# Fidgetspinner.net
KiCad netlist of a schematic drawn in EAGLE
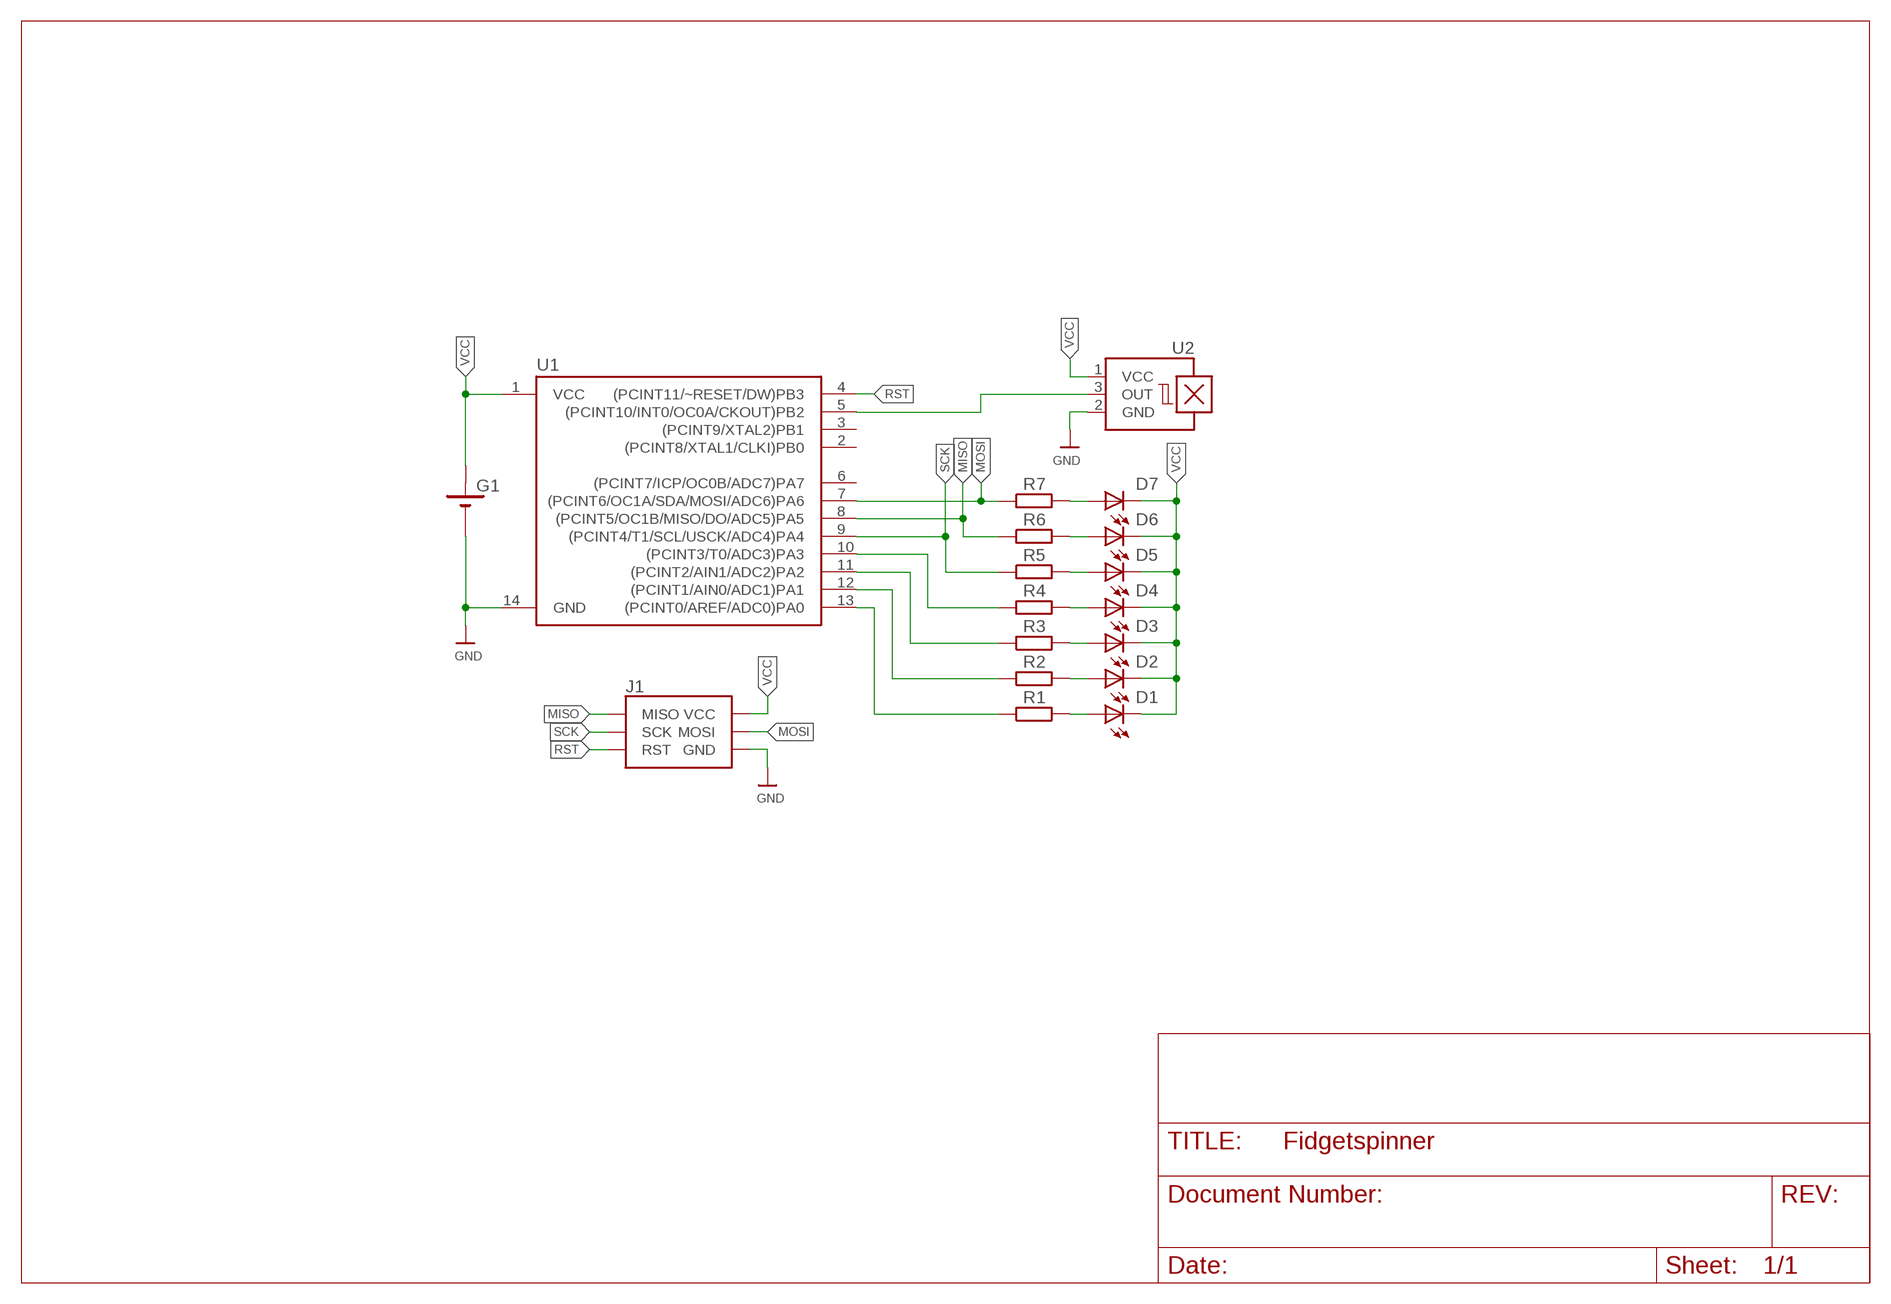
[diagram p0: schematic, sheet 1]

(export (version "E")
  (design (tool "Eeschema 10.0.6"))
  (components
    (comp (ref "D1")
      (value "LEDCHIPLED_0805")
      (footprint "eagle-import:CHIPLED_0805")
      (libsource (lib "eagle-import") (part "LEDCHIPLED_0805"))
    )
    (comp (ref "D2")
      (value "LEDCHIPLED_0805")
      (footprint "eagle-import:CHIPLED_0805")
      (libsource (lib "eagle-import") (part "LEDCHIPLED_0805"))
    )
    (comp (ref "D3")
      (value "LEDCHIPLED_0805")
      (footprint "eagle-import:CHIPLED_0805")
      (libsource (lib "eagle-import") (part "LEDCHIPLED_0805"))
    )
    (comp (ref "D4")
      (value "LEDCHIPLED_0805")
      (footprint "eagle-import:CHIPLED_0805")
      (libsource (lib "eagle-import") (part "LEDCHIPLED_0805"))
    )
    (comp (ref "D5")
      (value "LEDCHIPLED_0805")
      (footprint "eagle-import:CHIPLED_0805")
      (libsource (lib "eagle-import") (part "LEDCHIPLED_0805"))
    )
    (comp (ref "D6")
      (value "LEDCHIPLED_0805")
      (footprint "eagle-import:CHIPLED_0805")
      (libsource (lib "eagle-import") (part "LEDCHIPLED_0805"))
    )
    (comp (ref "D7")
      (value "LEDCHIPLED_0805")
      (footprint "eagle-import:CHIPLED_0805")
      (libsource (lib "eagle-import") (part "LEDCHIPLED_0805"))
    )
    (comp (ref "G1")
      (value "BATTERY")
      (footprint "eagle-import:10MM_SM_COIN_CELL_CLIP")
      (libsource (lib "eagle-import") (part "BATTERY"))
    )
    (comp (ref "J1")
      (value "SPI-HEADER2X3_LOCK")
      (footprint "eagle-import:2X3_LOCK")
      (libsource (lib "eagle-import") (part "SPI-HEADER2X3_LOCK"))
    )
    (comp (ref "R1")
      (value "RESISTOR0805")
      (footprint "eagle-import:0805")
      (libsource (lib "eagle-import") (part "RESISTOR0805"))
    )
    (comp (ref "R2")
      (value "RESISTOR0805")
      (footprint "eagle-import:0805")
      (libsource (lib "eagle-import") (part "RESISTOR0805"))
    )
    (comp (ref "R3")
      (value "RESISTOR0805")
      (footprint "eagle-import:0805")
      (libsource (lib "eagle-import") (part "RESISTOR0805"))
    )
    (comp (ref "R4")
      (value "RESISTOR0805")
      (footprint "eagle-import:0805")
      (libsource (lib "eagle-import") (part "RESISTOR0805"))
    )
    (comp (ref "R5")
      (value "RESISTOR0805")
      (footprint "eagle-import:0805")
      (libsource (lib "eagle-import") (part "RESISTOR0805"))
    )
    (comp (ref "R6")
      (value "RESISTOR0805")
      (footprint "eagle-import:0805")
      (libsource (lib "eagle-import") (part "RESISTOR0805"))
    )
    (comp (ref "R7")
      (value "RESISTOR0805")
      (footprint "eagle-import:0805")
      (libsource (lib "eagle-import") (part "RESISTOR0805"))
    )
    (comp (ref "U1")
      (value "ATTINY84ATTINY84-20PU")
      (footprint "eagle-import:DIP14")
      (libsource (lib "eagle-import") (part "ATTINY84ATTINY84-20PU"))
    )
    (comp (ref "U2")
      (value "HALL-SWITCH02UA")
      (footprint "eagle-import:SIP3-UA")
      (libsource (lib "eagle-import") (part "HALL-SWITCHUA02"))
    )
  )
  (nets
    (net (code "1") (name "GND") (class "Default")
      (node (ref "G1") (pin "-") (pinfunction "-_-") (pintype "passive"))
      (node (ref "J1") (pin "6") (pinfunction "GND_6") (pintype "passive"))
      (node (ref "U1") (pin "14") (pinfunction "GND_14") (pintype "bidirectional"))
      (node (ref "U2") (pin "2") (pinfunction "GND_2") (pintype "power_in"))
    )
    (net (code "2") (name "MISO") (class "Default")
      (node (ref "J1") (pin "1") (pinfunction "MISO_1") (pintype "passive"))
      (node (ref "R6") (pin "1") (pinfunction "1_1") (pintype "passive"))
      (node (ref "U1") (pin "8") (pinfunction "(PCINT5/OC1B/MISO/DO/ADC5)PA5_8") (pintype "bidirectional"))
    )
    (net (code "3") (name "MOSI") (class "Default")
      (node (ref "J1") (pin "4") (pinfunction "MOSI_4") (pintype "passive"))
      (node (ref "R7") (pin "1") (pinfunction "1_1") (pintype "passive"))
      (node (ref "U1") (pin "7") (pinfunction "(PCINT6/OC1A/SDA/MOSI/ADC6)PA6_7") (pintype "bidirectional"))
    )
    (net (code "4") (name "Net-(D1-PadA)") (class "Default")
      (node (ref "D1") (pin "A") (pinfunction "A_A") (pintype "passive"))
      (node (ref "R1") (pin "2") (pinfunction "2_2") (pintype "passive"))
    )
    (net (code "5") (name "Net-(D2-PadA)") (class "Default")
      (node (ref "D2") (pin "A") (pinfunction "A_A") (pintype "passive"))
      (node (ref "R2") (pin "2") (pinfunction "2_2") (pintype "passive"))
    )
    (net (code "6") (name "Net-(D3-PadA)") (class "Default")
      (node (ref "D3") (pin "A") (pinfunction "A_A") (pintype "passive"))
      (node (ref "R3") (pin "2") (pinfunction "2_2") (pintype "passive"))
    )
    (net (code "7") (name "Net-(D4-PadA)") (class "Default")
      (node (ref "D4") (pin "A") (pinfunction "A_A") (pintype "passive"))
      (node (ref "R4") (pin "2") (pinfunction "2_2") (pintype "passive"))
    )
    (net (code "8") (name "Net-(D5-PadA)") (class "Default")
      (node (ref "D5") (pin "A") (pinfunction "A_A") (pintype "passive"))
      (node (ref "R5") (pin "2") (pinfunction "2_2") (pintype "passive"))
    )
    (net (code "9") (name "Net-(D6-PadA)") (class "Default")
      (node (ref "D6") (pin "A") (pinfunction "A_A") (pintype "passive"))
      (node (ref "R6") (pin "2") (pinfunction "2_2") (pintype "passive"))
    )
    (net (code "10") (name "Net-(D7-PadA)") (class "Default")
      (node (ref "D7") (pin "A") (pinfunction "A_A") (pintype "passive"))
      (node (ref "R7") (pin "2") (pinfunction "2_2") (pintype "passive"))
    )
    (net (code "11") (name "Net-(U1-(PCINT0{slash}AREF{slash}ADC0)PA0)") (class "Default")
      (node (ref "R1") (pin "1") (pinfunction "1_1") (pintype "passive"))
      (node (ref "U1") (pin "13") (pinfunction "(PCINT0/AREF/ADC0)PA0_13") (pintype "bidirectional"))
    )
    (net (code "12") (name "Net-(U1-(PCINT1{slash}AIN0{slash}ADC1)PA1)") (class "Default")
      (node (ref "R2") (pin "1") (pinfunction "1_1") (pintype "passive"))
      (node (ref "U1") (pin "12") (pinfunction "(PCINT1/AIN0/ADC1)PA1_12") (pintype "bidirectional"))
    )
    (net (code "13") (name "Net-(U1-(PCINT2{slash}AIN1{slash}ADC2)PA2)") (class "Default")
      (node (ref "R3") (pin "1") (pinfunction "1_1") (pintype "passive"))
      (node (ref "U1") (pin "11") (pinfunction "(PCINT2/AIN1/ADC2)PA2_11") (pintype "bidirectional"))
    )
    (net (code "14") (name "Net-(U1-(PCINT3{slash}T0{slash}ADC3)PA3)") (class "Default")
      (node (ref "R4") (pin "1") (pinfunction "1_1") (pintype "passive"))
      (node (ref "U1") (pin "10") (pinfunction "(PCINT3/T0/ADC3)PA3_10") (pintype "bidirectional"))
    )
    (net (code "15") (name "Net-(U1-(PCINT10{slash}INT0{slash}OC0A{slash}CKOUT)PB2)") (class "Default")
      (node (ref "U1") (pin "5") (pinfunction "(PCINT10/INT0/OC0A/CKOUT)PB2_5") (pintype "bidirectional"))
      (node (ref "U2") (pin "3") (pinfunction "OUT_3") (pintype "output"))
    )
    (net (code "16") (name "RST") (class "Default")
      (node (ref "J1") (pin "5") (pinfunction "RST_5") (pintype "passive"))
      (node (ref "U1") (pin "4") (pinfunction "(PCINT11/~{RESET/DW})PB3_4") (pintype "bidirectional"))
    )
    (net (code "17") (name "SCK") (class "Default")
      (node (ref "J1") (pin "3") (pinfunction "SCK_3") (pintype "passive"))
      (node (ref "R5") (pin "1") (pinfunction "1_1") (pintype "passive"))
      (node (ref "U1") (pin "9") (pinfunction "(PCINT4/T1/SCL/USCK/ADC4)PA4_9") (pintype "bidirectional"))
    )
    (net (code "18") (name "VCC") (class "Default")
      (node (ref "D1") (pin "C") (pinfunction "C_C") (pintype "passive"))
      (node (ref "D2") (pin "C") (pinfunction "C_C") (pintype "passive"))
      (node (ref "D3") (pin "C") (pinfunction "C_C") (pintype "passive"))
      (node (ref "D4") (pin "C") (pinfunction "C_C") (pintype "passive"))
      (node (ref "D5") (pin "C") (pinfunction "C_C") (pintype "passive"))
      (node (ref "D6") (pin "C") (pinfunction "C_C") (pintype "passive"))
      (node (ref "D7") (pin "C") (pinfunction "C_C") (pintype "passive"))
      (node (ref "G1") (pin "+@1") (pinfunction "+_+@1") (pintype "passive"))
      (node (ref "G1") (pin "+@2") (pinfunction "+_+@2") (pintype "passive"))
      (node (ref "J1") (pin "2") (pinfunction "VCC_2") (pintype "passive"))
      (node (ref "U1") (pin "1") (pinfunction "VCC_1") (pintype "bidirectional"))
      (node (ref "U2") (pin "1") (pinfunction "VCC_1") (pintype "power_in"))
    )
    (net (code "19") (name "unconnected-(U1-(PCINT7{slash}ICP{slash}OC0B{slash}ADC7)PA7-Pad6)") (class "Default")
      (node (ref "U1") (pin "6") (pinfunction "(PCINT7/ICP/OC0B/ADC7)PA7_6") (pintype "bidirectional"))
    )
    (net (code "20") (name "unconnected-(U1-(PCINT8{slash}XTAL1{slash}CLKI)PB0-Pad2)") (class "Default")
      (node (ref "U1") (pin "2") (pinfunction "(PCINT8/XTAL1/CLKI)PB0_2") (pintype "bidirectional"))
    )
    (net (code "21") (name "unconnected-(U1-(PCINT9{slash}XTAL2)PB1-Pad3)") (class "Default")
      (node (ref "U1") (pin "3") (pinfunction "(PCINT9/XTAL2)PB1_3") (pintype "bidirectional"))
    )
  )
)
